# sparkroad_sheet1.net
KiCad netlist of a schematic drawn in Altium Designer
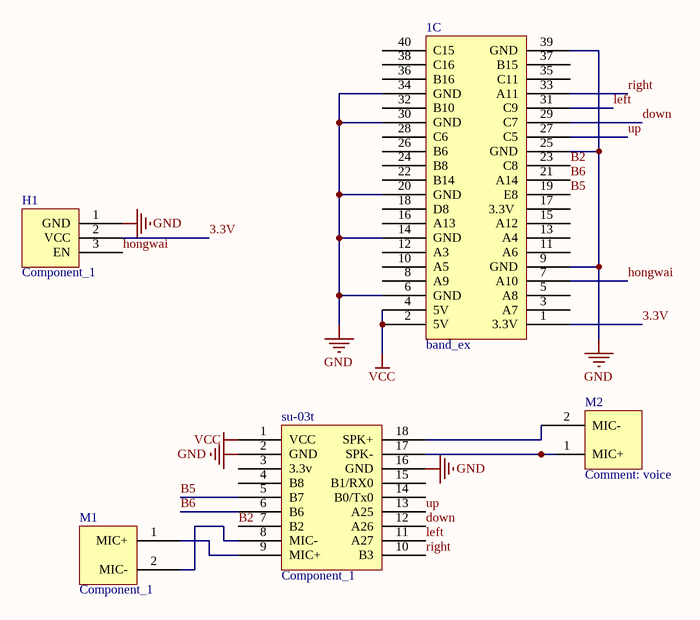
[diagram p0: sparkroad_sheet1.SchDoc]

(export (version "E")
  (design (tool "Eeschema 10.0.6"))
  (components
    (comp (ref "1")
      (value "band_ex")
      (footprint "HDR2X20")
      (libsource (lib "sparkroad_ex_20x2") (part "Component_1"))
    )
    (comp (ref "H1")
      (value "Component_1")
      (footprint "HDR1X3")
      (libsource (lib "hongwai") (part "Component_1"))
    )
    (comp (ref "M1")
      (value "Component_1")
      (footprint "PCBComponent_1")
      (libsource (lib "") (part "Component_1_1"))
    )
    (comp (ref "M2")
      (value "voice")
      (footprint "PCBComponent_1")
      (libsource (lib "mitou") (part "Component_1"))
    )
    (comp (ref "su-03t")
      (value "Component_1")
      (footprint "SU-03T")
      (libsource (lib "su-03t") (part "Component_1"))
    )
  )
  (nets
    (net (code "1") (name "/3.3V") (class "Default")
      (node (ref "1") (pin "1") (pinfunction "3.3V_1") (pintype "passive"))
      (node (ref "H1") (pin "2") (pinfunction "VCC_2") (pintype "passive"))
    )
    (net (code "2") (name "/B2") (class "Default")
      (node (ref "1") (pin "23") (pinfunction "C8_23") (pintype "passive"))
      (node (ref "su-03t") (pin "7") (pinfunction "B2_7") (pintype "passive"))
    )
    (net (code "3") (name "/B5") (class "Default")
      (node (ref "1") (pin "19") (pinfunction "E8_19") (pintype "passive"))
      (node (ref "su-03t") (pin "5") (pinfunction "B7_5") (pintype "passive"))
    )
    (net (code "4") (name "/B6") (class "Default")
      (node (ref "1") (pin "21") (pinfunction "A14_21") (pintype "passive"))
      (node (ref "su-03t") (pin "6") (pinfunction "B6_6") (pintype "passive"))
    )
    (net (code "5") (name "/down") (class "Default")
      (node (ref "1") (pin "29") (pinfunction "C7_29") (pintype "passive"))
      (node (ref "su-03t") (pin "12") (pinfunction "A26_12") (pintype "passive"))
    )
    (net (code "6") (name "/hongwai") (class "Default")
      (node (ref "1") (pin "7") (pinfunction "A10_7") (pintype "passive"))
      (node (ref "H1") (pin "3") (pinfunction "EN_3") (pintype "passive"))
    )
    (net (code "7") (name "/left") (class "Default")
      (node (ref "1") (pin "31") (pinfunction "C9_31") (pintype "passive"))
      (node (ref "su-03t") (pin "11") (pinfunction "A27_11") (pintype "passive"))
    )
    (net (code "8") (name "/right") (class "Default")
      (node (ref "1") (pin "33") (pinfunction "A11_33") (pintype "passive"))
      (node (ref "su-03t") (pin "10") (pinfunction "B3_10") (pintype "passive"))
    )
    (net (code "9") (name "/up") (class "Default")
      (node (ref "1") (pin "27") (pinfunction "C5_27") (pintype "passive"))
      (node (ref "su-03t") (pin "13") (pinfunction "A25_13") (pintype "passive"))
    )
    (net (code "10") (name "GND") (class "Default")
      (node (ref "1") (pin "14") (pinfunction "GND_14") (pintype "passive"))
      (node (ref "1") (pin "20") (pinfunction "GND_20") (pintype "passive"))
      (node (ref "1") (pin "25") (pinfunction "GND_25") (pintype "passive"))
      (node (ref "1") (pin "30") (pinfunction "GND_30") (pintype "passive"))
      (node (ref "1") (pin "34") (pinfunction "GND_34") (pintype "passive"))
      (node (ref "1") (pin "39") (pinfunction "GND_39") (pintype "passive"))
      (node (ref "1") (pin "6") (pinfunction "GND_6") (pintype "passive"))
      (node (ref "1") (pin "9") (pinfunction "GND_9") (pintype "passive"))
      (node (ref "H1") (pin "1") (pinfunction "GND_1") (pintype "passive"))
      (node (ref "su-03t") (pin "16") (pinfunction "GND_16") (pintype "passive"))
      (node (ref "su-03t") (pin "2") (pinfunction "GND_2") (pintype "passive"))
    )
    (net (code "11") (name "Net-(M1-MIC+)") (class "Default")
      (node (ref "M1") (pin "1") (pinfunction "MIC+_1") (pintype "passive"))
      (node (ref "su-03t") (pin "9") (pinfunction "MIC+_9") (pintype "passive"))
    )
    (net (code "12") (name "Net-(M1-MIC-)") (class "Default")
      (node (ref "M1") (pin "2") (pinfunction "MIC-_2") (pintype "passive"))
      (node (ref "su-03t") (pin "8") (pinfunction "MIC-_8") (pintype "passive"))
    )
    (net (code "13") (name "Net-(M2-MIC+)") (class "Default")
      (node (ref "M2") (pin "1") (pinfunction "MIC+_1") (pintype "passive"))
      (node (ref "su-03t") (pin "17") (pinfunction "SPK-_17") (pintype "passive"))
    )
    (net (code "14") (name "Net-(M2-MIC-)") (class "Default")
      (node (ref "M2") (pin "2") (pinfunction "MIC-_2") (pintype "passive"))
      (node (ref "su-03t") (pin "18") (pinfunction "SPK+_18") (pintype "passive"))
    )
    (net (code "15") (name "VCC") (class "Default")
      (node (ref "1") (pin "2") (pinfunction "5V_2") (pintype "passive"))
      (node (ref "1") (pin "4") (pinfunction "5V_4") (pintype "passive"))
      (node (ref "su-03t") (pin "1") (pinfunction "VCC_1") (pintype "passive"))
    )
    (net (code "16") (name "unconnected-(1C-3.3V-Pad17)") (class "Default")
      (node (ref "1") (pin "17") (pinfunction "3.3V_17") (pintype "passive"))
    )
    (net (code "17") (name "unconnected-(1C-A3-Pad12)") (class "Default")
      (node (ref "1") (pin "12") (pinfunction "A3_12") (pintype "passive"))
    )
    (net (code "18") (name "unconnected-(1C-A4-Pad13)") (class "Default")
      (node (ref "1") (pin "13") (pinfunction "A4_13") (pintype "passive"))
    )
    (net (code "19") (name "unconnected-(1C-A5-Pad10)") (class "Default")
      (node (ref "1") (pin "10") (pinfunction "A5_10") (pintype "passive"))
    )
    (net (code "20") (name "unconnected-(1C-A6-Pad11)") (class "Default")
      (node (ref "1") (pin "11") (pinfunction "A6_11") (pintype "passive"))
    )
    (net (code "21") (name "unconnected-(1C-A7-Pad3)") (class "Default")
      (node (ref "1") (pin "3") (pinfunction "A7_3") (pintype "passive"))
    )
    (net (code "22") (name "unconnected-(1C-A8-Pad5)") (class "Default")
      (node (ref "1") (pin "5") (pinfunction "A8_5") (pintype "passive"))
    )
    (net (code "23") (name "unconnected-(1C-A9-Pad8)") (class "Default")
      (node (ref "1") (pin "8") (pinfunction "A9_8") (pintype "passive"))
    )
    (net (code "24") (name "unconnected-(1C-A12-Pad15)") (class "Default")
      (node (ref "1") (pin "15") (pinfunction "A12_15") (pintype "passive"))
    )
    (net (code "25") (name "unconnected-(1C-A13-Pad16)") (class "Default")
      (node (ref "1") (pin "16") (pinfunction "A13_16") (pintype "passive"))
    )
    (net (code "26") (name "unconnected-(1C-B6-Pad26)") (class "Default")
      (node (ref "1") (pin "26") (pinfunction "B6_26") (pintype "passive"))
    )
    (net (code "27") (name "unconnected-(1C-B8-Pad24)") (class "Default")
      (node (ref "1") (pin "24") (pinfunction "B8_24") (pintype "passive"))
    )
    (net (code "28") (name "unconnected-(1C-B10-Pad32)") (class "Default")
      (node (ref "1") (pin "32") (pinfunction "B10_32") (pintype "passive"))
    )
    (net (code "29") (name "unconnected-(1C-B14-Pad22)") (class "Default")
      (node (ref "1") (pin "22") (pinfunction "B14_22") (pintype "passive"))
    )
    (net (code "30") (name "unconnected-(1C-B15-Pad37)") (class "Default")
      (node (ref "1") (pin "37") (pinfunction "B15_37") (pintype "passive"))
    )
    (net (code "31") (name "unconnected-(1C-B16-Pad36)") (class "Default")
      (node (ref "1") (pin "36") (pinfunction "B16_36") (pintype "passive"))
    )
    (net (code "32") (name "unconnected-(1C-C6-Pad28)") (class "Default")
      (node (ref "1") (pin "28") (pinfunction "C6_28") (pintype "passive"))
    )
    (net (code "33") (name "unconnected-(1C-C11-Pad35)") (class "Default")
      (node (ref "1") (pin "35") (pinfunction "C11_35") (pintype "passive"))
    )
    (net (code "34") (name "unconnected-(1C-C15-Pad40)") (class "Default")
      (node (ref "1") (pin "40") (pinfunction "C15_40") (pintype "passive"))
    )
    (net (code "35") (name "unconnected-(1C-C16-Pad38)") (class "Default")
      (node (ref "1") (pin "38") (pinfunction "C16_38") (pintype "passive"))
    )
    (net (code "36") (name "unconnected-(1C-D8-Pad18)") (class "Default")
      (node (ref "1") (pin "18") (pinfunction "D8_18") (pintype "passive"))
    )
    (net (code "37") (name "unconnected-(su-03t-3.3v-Pad3)") (class "Default")
      (node (ref "su-03t") (pin "3") (pinfunction "3.3v_3") (pintype "passive"))
    )
    (net (code "38") (name "unconnected-(su-03t-B0{slash}Tx0-Pad14)") (class "Default")
      (node (ref "su-03t") (pin "14") (pinfunction "B0/Tx0_14") (pintype "passive"))
    )
    (net (code "39") (name "unconnected-(su-03t-B1{slash}RX0-Pad15)") (class "Default")
      (node (ref "su-03t") (pin "15") (pinfunction "B1/RX0_15") (pintype "passive"))
    )
    (net (code "40") (name "unconnected-(su-03t-B8-Pad4)") (class "Default")
      (node (ref "su-03t") (pin "4") (pinfunction "B8_4") (pintype "passive"))
    )
  )
)
